# FootKeyboardTrial_16F1459.net
KiCad netlist of a schematic drawn in EAGLE
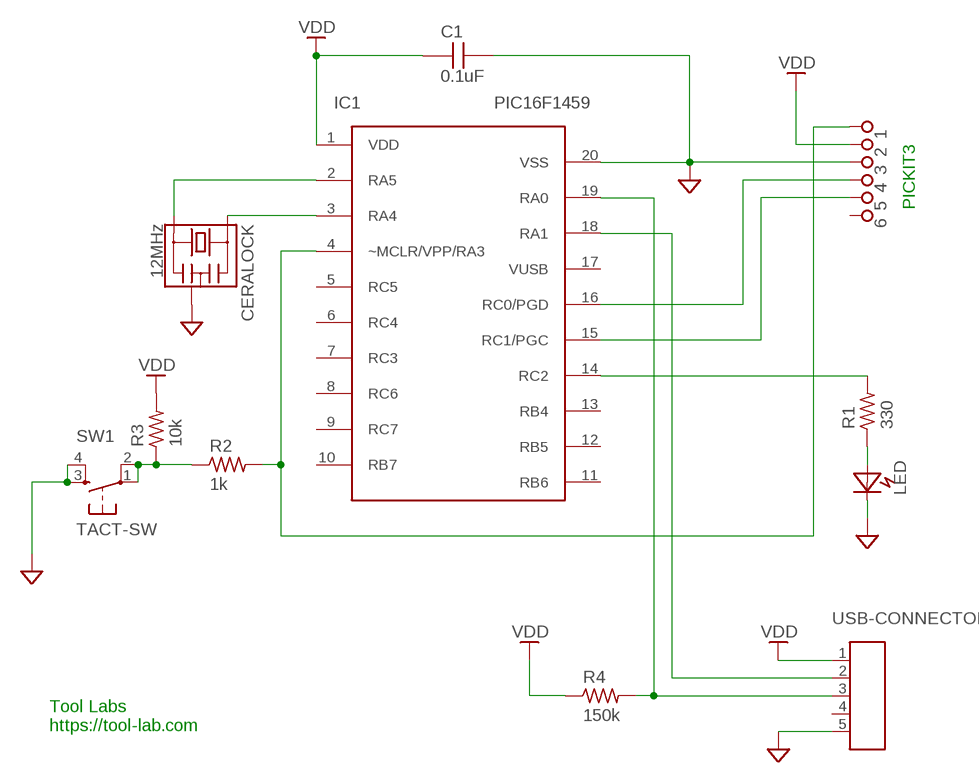
[diagram p0: schematic, sheet 1]

(export (version "E")
  (design (tool "Eeschema 10.0.6"))
  (components
    (comp (ref "1")
      (value "TP1")
      (footprint "eagle-import:TP1")
      (libsource (lib "eagle-import") (part "TP1"))
    )
    (comp (ref "2")
      (value "TP1")
      (footprint "eagle-import:TP1")
      (libsource (lib "eagle-import") (part "TP1"))
    )
    (comp (ref "3")
      (value "TP1")
      (footprint "eagle-import:TP1")
      (libsource (lib "eagle-import") (part "TP1"))
    )
    (comp (ref "4")
      (value "TP1")
      (footprint "eagle-import:TP1")
      (libsource (lib "eagle-import") (part "TP1"))
    )
    (comp (ref "5")
      (value "TP1")
      (footprint "eagle-import:TP1")
      (libsource (lib "eagle-import") (part "TP1"))
    )
    (comp (ref "6")
      (value "TP1")
      (footprint "eagle-import:TP1")
      (libsource (lib "eagle-import") (part "TP1"))
    )
    (comp (ref "C1")
      (value "0.1uF")
      (footprint "eagle-import:CAP_10X4")
      (libsource (lib "eagle-import") (part "CAP10X4"))
    )
    (comp (ref "CERALOCK")
      (value "12MHz")
      (footprint "eagle-import:CSTLS")
      (libsource (lib "eagle-import") (part "CERALOCK"))
    )
    (comp (ref "IC1")
      (value "PIC16F1459")
      (footprint "eagle-import:DIL20")
      (libsource (lib "eagle-import") (part "PIC16F145XPIC16F145X"))
    )
    (comp (ref "LED")
      (value "LED")
      (footprint "eagle-import:LED_3MM_VIRT_2")
      (libsource (lib "eagle-import") (part "LED"))
    )
    (comp (ref "R1")
      (value "330")
      (footprint "eagle-import:R_0.5W_5")
      (libsource (lib "eagle-import") (part "R0.5W_5P"))
    )
    (comp (ref "R2")
      (value "1k")
      (footprint "eagle-import:R_0.5W_5")
      (libsource (lib "eagle-import") (part "R0.5W_5P"))
    )
    (comp (ref "R3")
      (value "10k")
      (footprint "eagle-import:R_0.5W_5")
      (libsource (lib "eagle-import") (part "R0.5W_5P"))
    )
    (comp (ref "R4")
      (value "150k")
      (footprint "eagle-import:R_0.5W_5")
      (libsource (lib "eagle-import") (part "R0.5W_5P"))
    )
    (comp (ref "SW1")
      (value "TACT-SW")
      (footprint "eagle-import:B3F-10X")
      (libsource (lib "eagle-import") (part "TACT-SW"))
    )
    (comp (ref "USB-CONNECTOR")
      (value "CON_5P")
      (footprint "eagle-import:CON_HRS_DIP_5")
      (libsource (lib "eagle-import") (part "CON_5P"))
    )
  )
  (nets
    (net (code "1") (name "GND") (class "Default")
      (node (ref "3") (pin "P$1") (pinfunction "P$1_P$1") (pintype "passive"))
      (node (ref "C1") (pin "2") (pinfunction "2_2") (pintype "passive"))
      (node (ref "CERALOCK") (pin "2") (pinfunction "2_2") (pintype "power_in"))
      (node (ref "IC1") (pin "20") (pinfunction "VSS_20") (pintype "bidirectional"))
      (node (ref "LED") (pin "K") (pinfunction "K_K") (pintype "passive"))
      (node (ref "SW1") (pin "3") (pinfunction "S_3") (pintype "passive"))
      (node (ref "SW1") (pin "4") (pinfunction "S1_4") (pintype "passive"))
      (node (ref "USB-CONNECTOR") (pin "5") (pinfunction "5_5") (pintype "passive"))
    )
    (net (code "2") (name "Net-(IC1-RA0)") (class "Default")
      (node (ref "IC1") (pin "19") (pinfunction "RA0_19") (pintype "bidirectional"))
      (node (ref "R4") (pin "2") (pinfunction "2_2") (pintype "passive"))
      (node (ref "USB-CONNECTOR") (pin "3") (pinfunction "3_3") (pintype "passive"))
    )
    (net (code "3") (name "Net-(IC1-RA1)") (class "Default")
      (node (ref "IC1") (pin "18") (pinfunction "RA1_18") (pintype "bidirectional"))
      (node (ref "USB-CONNECTOR") (pin "2") (pinfunction "2_2") (pintype "passive"))
    )
    (net (code "4") (name "Net-(IC1-RA4)") (class "Default")
      (node (ref "CERALOCK") (pin "1") (pinfunction "1_1") (pintype "passive"))
      (node (ref "IC1") (pin "3") (pinfunction "RA4_3") (pintype "bidirectional"))
    )
    (net (code "5") (name "Net-(IC1-RA5)") (class "Default")
      (node (ref "CERALOCK") (pin "3") (pinfunction "3_3") (pintype "passive"))
      (node (ref "IC1") (pin "2") (pinfunction "RA5_2") (pintype "bidirectional"))
    )
    (net (code "6") (name "Net-(IC1-RC0{slash}PGD)") (class "Default")
      (node (ref "4") (pin "P$1") (pinfunction "P$1_P$1") (pintype "passive"))
      (node (ref "IC1") (pin "16") (pinfunction "RC0/PGD_16") (pintype "bidirectional"))
    )
    (net (code "7") (name "Net-(IC1-RC1{slash}PGC)") (class "Default")
      (node (ref "5") (pin "P$1") (pinfunction "P$1_P$1") (pintype "passive"))
      (node (ref "IC1") (pin "15") (pinfunction "RC1/PGC_15") (pintype "bidirectional"))
    )
    (net (code "8") (name "Net-(IC1-RC2)") (class "Default")
      (node (ref "IC1") (pin "14") (pinfunction "RC2_14") (pintype "bidirectional"))
      (node (ref "R1") (pin "2") (pinfunction "2_2") (pintype "passive"))
    )
    (net (code "9") (name "Net-(IC1-~{MCLR{slash}VPP{slash}RA3})") (class "Default")
      (node (ref "1") (pin "P$1") (pinfunction "P$1_P$1") (pintype "passive"))
      (node (ref "IC1") (pin "4") (pinfunction "~{MCLR/VPP/RA3}_4") (pintype "bidirectional"))
      (node (ref "R2") (pin "2") (pinfunction "2_2") (pintype "passive"))
    )
    (net (code "10") (name "Net-(LED-PadA)") (class "Default")
      (node (ref "LED") (pin "A") (pinfunction "A_A") (pintype "passive"))
      (node (ref "R1") (pin "1") (pinfunction "1_1") (pintype "passive"))
    )
    (net (code "11") (name "Net-(SW1-P)") (class "Default")
      (node (ref "R2") (pin "1") (pinfunction "1_1") (pintype "passive"))
      (node (ref "R3") (pin "1") (pinfunction "1_1") (pintype "passive"))
      (node (ref "SW1") (pin "1") (pinfunction "P_1") (pintype "passive"))
      (node (ref "SW1") (pin "2") (pinfunction "P1_2") (pintype "passive"))
    )
    (net (code "12") (name "VDD") (class "Default")
      (node (ref "2") (pin "P$1") (pinfunction "P$1_P$1") (pintype "passive"))
      (node (ref "C1") (pin "1") (pinfunction "1_1") (pintype "passive"))
      (node (ref "IC1") (pin "1") (pinfunction "VDD_1") (pintype "bidirectional"))
      (node (ref "R3") (pin "2") (pinfunction "2_2") (pintype "passive"))
      (node (ref "R4") (pin "1") (pinfunction "1_1") (pintype "passive"))
      (node (ref "USB-CONNECTOR") (pin "1") (pinfunction "1_1") (pintype "passive"))
    )
    (net (code "13") (name "unconnected-(6-PadP$1)") (class "Default")
      (node (ref "6") (pin "P$1") (pinfunction "P$1_P$1") (pintype "passive"))
    )
    (net (code "14") (name "unconnected-(IC1-RB4-Pad13)") (class "Default")
      (node (ref "IC1") (pin "13") (pinfunction "RB4_13") (pintype "bidirectional"))
    )
    (net (code "15") (name "unconnected-(IC1-RB5-Pad12)") (class "Default")
      (node (ref "IC1") (pin "12") (pinfunction "RB5_12") (pintype "bidirectional"))
    )
    (net (code "16") (name "unconnected-(IC1-RB6-Pad11)") (class "Default")
      (node (ref "IC1") (pin "11") (pinfunction "RB6_11") (pintype "bidirectional"))
    )
    (net (code "17") (name "unconnected-(IC1-RB7-Pad10)") (class "Default")
      (node (ref "IC1") (pin "10") (pinfunction "RB7_10") (pintype "bidirectional"))
    )
    (net (code "18") (name "unconnected-(IC1-RC3-Pad7)") (class "Default")
      (node (ref "IC1") (pin "7") (pinfunction "RC3_7") (pintype "bidirectional"))
    )
    (net (code "19") (name "unconnected-(IC1-RC4-Pad6)") (class "Default")
      (node (ref "IC1") (pin "6") (pinfunction "RC4_6") (pintype "bidirectional"))
    )
    (net (code "20") (name "unconnected-(IC1-RC5-Pad5)") (class "Default")
      (node (ref "IC1") (pin "5") (pinfunction "RC5_5") (pintype "bidirectional"))
    )
    (net (code "21") (name "unconnected-(IC1-RC6-Pad8)") (class "Default")
      (node (ref "IC1") (pin "8") (pinfunction "RC6_8") (pintype "bidirectional"))
    )
    (net (code "22") (name "unconnected-(IC1-RC7-Pad9)") (class "Default")
      (node (ref "IC1") (pin "9") (pinfunction "RC7_9") (pintype "bidirectional"))
    )
    (net (code "23") (name "unconnected-(IC1-VUSB-Pad17)") (class "Default")
      (node (ref "IC1") (pin "17") (pinfunction "VUSB_17") (pintype "bidirectional"))
    )
    (net (code "24") (name "unconnected-(USB-CONNECTOR-Pad4)") (class "Default")
      (node (ref "USB-CONNECTOR") (pin "4") (pinfunction "4_4") (pintype "passive"))
    )
  )
)
